# telemetry-r1.net
KiCad netlist of a schematic drawn in EAGLE
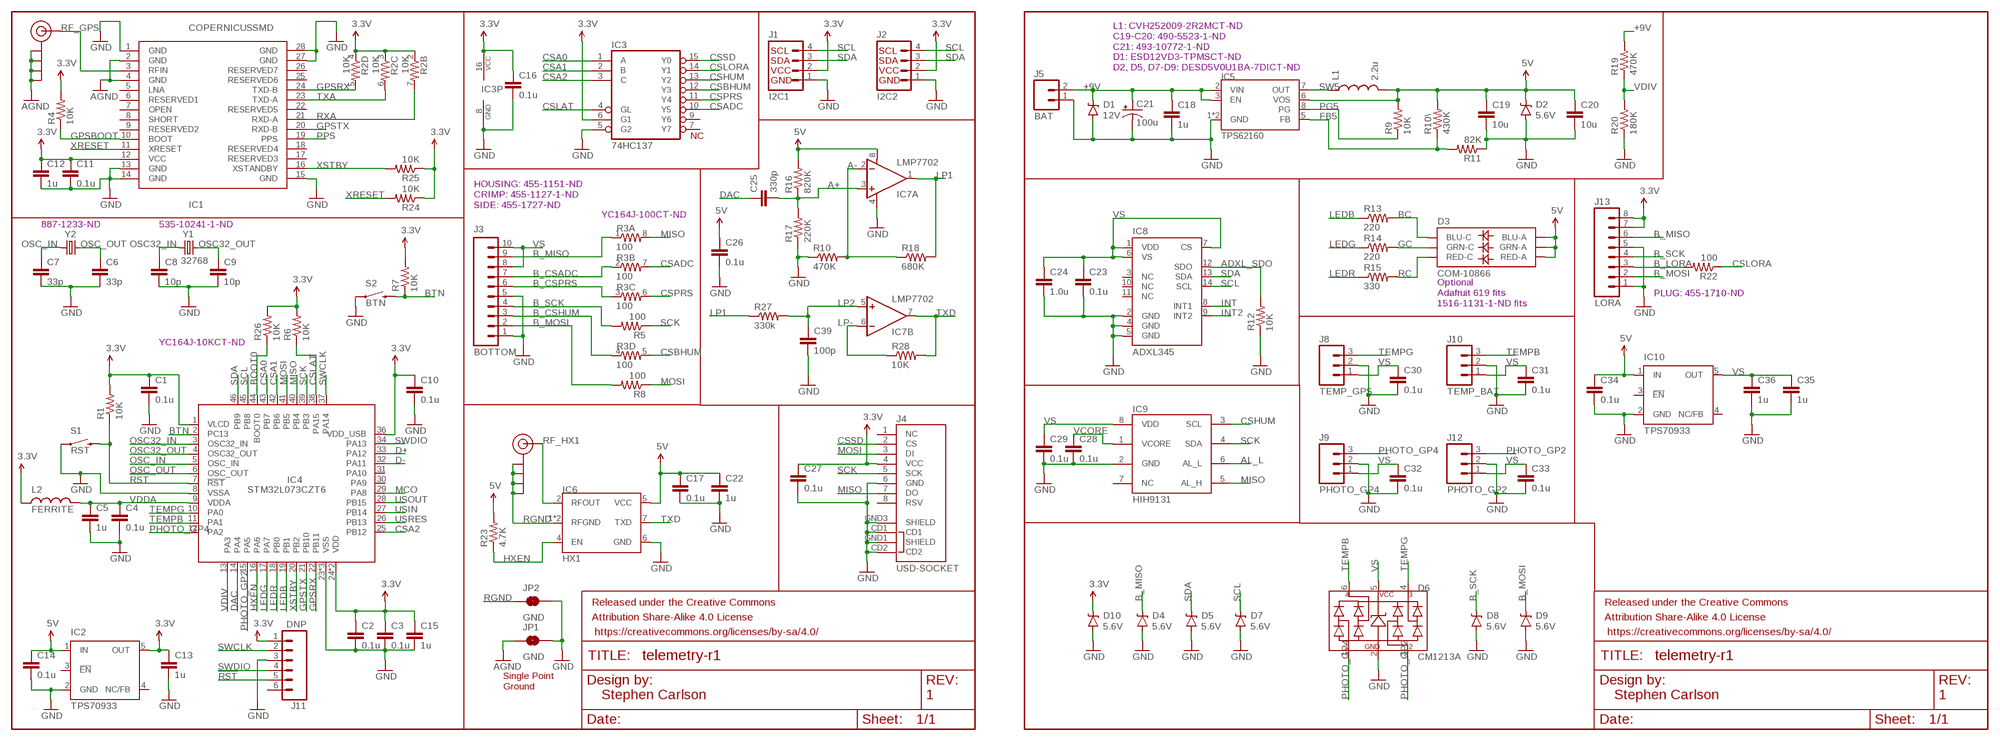
[diagram p0: schematic, sheet 1]

(export (version "E")
  (design (tool "Eeschema 10.0.6"))
  (components
    (comp (ref "C1")
      (value "0.1u")
      (footprint "eagle-import:0805")
      (libsource (lib "eagle-import") (part "CAP0805"))
    )
    (comp (ref "C2")
      (value "0.1u")
      (footprint "eagle-import:0805")
      (libsource (lib "eagle-import") (part "CAP0805"))
    )
    (comp (ref "C3")
      (value "0.1u")
      (footprint "eagle-import:0805")
      (libsource (lib "eagle-import") (part "CAP0805"))
    )
    (comp (ref "C4")
      (value "0.1u")
      (footprint "eagle-import:0805")
      (libsource (lib "eagle-import") (part "CAP0805"))
    )
    (comp (ref "C5")
      (value "1u")
      (footprint "eagle-import:0805")
      (libsource (lib "eagle-import") (part "CAP0805"))
    )
    (comp (ref "C6")
      (value "33p")
      (footprint "eagle-import:0805")
      (libsource (lib "eagle-import") (part "CAP0805"))
    )
    (comp (ref "C7")
      (value "33p")
      (footprint "eagle-import:0805")
      (libsource (lib "eagle-import") (part "CAP0805"))
    )
    (comp (ref "C8")
      (value "10p")
      (footprint "eagle-import:0805")
      (libsource (lib "eagle-import") (part "CAP0805"))
    )
    (comp (ref "C9")
      (value "10p")
      (footprint "eagle-import:0805")
      (libsource (lib "eagle-import") (part "CAP0805"))
    )
    (comp (ref "C10")
      (value "0.1u")
      (footprint "eagle-import:0805")
      (libsource (lib "eagle-import") (part "CAP0805"))
    )
    (comp (ref "C11")
      (value "0.1u")
      (footprint "eagle-import:0805")
      (libsource (lib "eagle-import") (part "CAP0805"))
    )
    (comp (ref "C12")
      (value "1u")
      (footprint "eagle-import:0805")
      (libsource (lib "eagle-import") (part "CAP0805"))
    )
    (comp (ref "C13")
      (value "1u")
      (footprint "eagle-import:0805")
      (libsource (lib "eagle-import") (part "CAP0805"))
    )
    (comp (ref "C14")
      (value "0.1u")
      (footprint "eagle-import:0805")
      (libsource (lib "eagle-import") (part "CAP0805"))
    )
    (comp (ref "C15")
      (value "1u")
      (footprint "eagle-import:0805")
      (libsource (lib "eagle-import") (part "CAP0805"))
    )
    (comp (ref "C16")
      (value "0.1u")
      (footprint "eagle-import:0805")
      (libsource (lib "eagle-import") (part "CAP0805"))
    )
    (comp (ref "C17")
      (value "0.1u")
      (footprint "eagle-import:0805")
      (libsource (lib "eagle-import") (part "CAP0805"))
    )
    (comp (ref "C18")
      (value "1u")
      (footprint "eagle-import:0805")
      (libsource (lib "eagle-import") (part "CAP0805"))
    )
    (comp (ref "C19")
      (value "10u")
      (footprint "eagle-import:0805")
      (libsource (lib "eagle-import") (part "CAP0805"))
    )
    (comp (ref "C20")
      (value "10u")
      (footprint "eagle-import:0805")
      (libsource (lib "eagle-import") (part "CAP0805"))
    )
    (comp (ref "C21")
      (value "100u")
      (footprint "eagle-import:CPOL-RADIAL-10UF-25V")
      (libsource (lib "eagle-import") (part "CAP_POLPTH2"))
    )
    (comp (ref "C22")
      (value "1u")
      (footprint "eagle-import:0805")
      (libsource (lib "eagle-import") (part "CAP0805"))
    )
    (comp (ref "C23")
      (value "0.1u")
      (footprint "eagle-import:0805")
      (libsource (lib "eagle-import") (part "CAP0805"))
    )
    (comp (ref "C24")
      (value "1.0u")
      (footprint "eagle-import:0805")
      (libsource (lib "eagle-import") (part "CAP0805"))
    )
    (comp (ref "C25")
      (value "330p")
      (footprint "eagle-import:0805")
      (libsource (lib "eagle-import") (part "CAP0805"))
    )
    (comp (ref "C26")
      (value "0.1u")
      (footprint "eagle-import:0805")
      (libsource (lib "eagle-import") (part "CAP0805"))
    )
    (comp (ref "C27")
      (value "0.1u")
      (footprint "eagle-import:0805")
      (libsource (lib "eagle-import") (part "CAP0805"))
    )
    (comp (ref "C28")
      (value "0.1u")
      (footprint "eagle-import:0805")
      (libsource (lib "eagle-import") (part "CAP0805"))
    )
    (comp (ref "C29")
      (value "0.1u")
      (footprint "eagle-import:0805")
      (libsource (lib "eagle-import") (part "CAP0805"))
    )
    (comp (ref "C30")
      (value "0.1u")
      (footprint "eagle-import:0805")
      (libsource (lib "eagle-import") (part "CAP0805"))
    )
    (comp (ref "C31")
      (value "0.1u")
      (footprint "eagle-import:0805")
      (libsource (lib "eagle-import") (part "CAP0805"))
    )
    (comp (ref "C32")
      (value "0.1u")
      (footprint "eagle-import:0805")
      (libsource (lib "eagle-import") (part "CAP0805"))
    )
    (comp (ref "C33")
      (value "0.1u")
      (footprint "eagle-import:0805")
      (libsource (lib "eagle-import") (part "CAP0805"))
    )
    (comp (ref "C34")
      (value "0.1u")
      (footprint "eagle-import:0805")
      (libsource (lib "eagle-import") (part "CAP0805"))
    )
    (comp (ref "C35")
      (value "1u")
      (footprint "eagle-import:0805")
      (libsource (lib "eagle-import") (part "CAP0805"))
    )
    (comp (ref "C36")
      (value "1u")
      (footprint "eagle-import:0805")
      (libsource (lib "eagle-import") (part "CAP0805"))
    )
    (comp (ref "C39")
      (value "100p")
      (footprint "eagle-import:0805")
      (libsource (lib "eagle-import") (part "CAP0805"))
    )
    (comp (ref "D1")
      (value "12V")
      (footprint "eagle-import:SOD-323")
      (libsource (lib "eagle-import") (part "DIODE-ZENER5.6V"))
    )
    (comp (ref "D2")
      (value "5.6V")
      (footprint "eagle-import:SOD-323")
      (libsource (lib "eagle-import") (part "DIODE-ZENER5.6V"))
    )
    (comp (ref "D3")
      (value "COM-10866")
      (footprint "eagle-import:LED-TRICOLOR-5050")
      (libsource (lib "eagle-import") (part "LED-TRICOLOR-5050NO_IC"))
    )
    (comp (ref "D4")
      (value "5.6V")
      (footprint "eagle-import:SOD-323")
      (libsource (lib "eagle-import") (part "DIODE-ZENER5.6V"))
    )
    (comp (ref "D5")
      (value "5.6V")
      (footprint "eagle-import:SOD-323")
      (libsource (lib "eagle-import") (part "DIODE-ZENER5.6V"))
    )
    (comp (ref "D6")
      (value "CM1213A")
      (footprint "eagle-import:SC70-6L")
      (libsource (lib "eagle-import") (part "CM1213A"))
    )
    (comp (ref "D7")
      (value "5.6V")
      (footprint "eagle-import:SOD-323")
      (libsource (lib "eagle-import") (part "DIODE-ZENER5.6V"))
    )
    (comp (ref "D8")
      (value "5.6V")
      (footprint "eagle-import:SOD-323")
      (libsource (lib "eagle-import") (part "DIODE-ZENER5.6V"))
    )
    (comp (ref "D9")
      (value "5.6V")
      (footprint "eagle-import:SOD-323")
      (libsource (lib "eagle-import") (part "DIODE-ZENER5.6V"))
    )
    (comp (ref "D10")
      (value "5.6V")
      (footprint "eagle-import:SOD-323")
      (libsource (lib "eagle-import") (part "DIODE-ZENER5.6V"))
    )
    (comp (ref "FRAME1")
      (value "FRAME-LETTERNO_PACKAGE")
      (footprint "eagle-import:DUMMY")
      (fields (field (name "DESIGNER") "Nobody"))
      (libsource (lib "eagle-import") (part "FRAME-LETTERNO_PACKAGE"))
    )
    (comp (ref "FRAME2")
      (value "FRAME-LETTERNO_PACKAGE")
      (footprint "eagle-import:DUMMY")
      (fields (field (name "DESIGNER") "Nobody"))
      (libsource (lib "eagle-import") (part "FRAME-LETTERNO_PACKAGE"))
    )
    (comp (ref "IC1")
      (value "COPERNICUSSMD")
      (footprint "eagle-import:COPERNICUS")
      (libsource (lib "eagle-import") (part "COPERNICUSSMD"))
    )
    (comp (ref "IC2")
      (value "TPS70933")
      (footprint "eagle-import:SOT23-DBV")
      (fields (field (name "MF") "TEXAS INSTRUMENTS") (field (name "MPN") "TPS77033DBVT"))
      (libsource (lib "eagle-import") (part "TPS77033"))
    )
    (comp (ref "IC3")
      (value "74HC137")
      (footprint "eagle-import:TSSOP16")
      (libsource (lib "eagle-import") (part "74137PWLS"))
    )
    (comp (ref "IC4")
      (value "STM32L073CZT6")
      (footprint "eagle-import:TQFP48")
      (libsource (lib "eagle-import") (part "STM32L07C"))
    )
    (comp (ref "IC5")
      (value "TPS62160")
      (footprint "eagle-import:MSOP8")
      (libsource (lib "eagle-import") (part "TPS62160"))
    )
    (comp (ref "IC6")
      (value "HX1")
      (footprint "eagle-import:HX1")
      (libsource (lib "eagle-import") (part "HX1"))
    )
    (comp (ref "IC7")
      (value "LMP7702")
      (footprint "eagle-import:SO08")
      (libsource (lib "eagle-import") (part "OPAMP-DUALU"))
    )
    (comp (ref "IC8")
      (value "ADXL345")
      (footprint "eagle-import:LGA14")
      (libsource (lib "eagle-import") (part "ADXL345"))
    )
    (comp (ref "IC9")
      (value "HIH9131")
      (footprint "eagle-import:SOIC8")
      (libsource (lib "eagle-import") (part "HIH6131"))
    )
    (comp (ref "IC10")
      (value "TPS70933")
      (footprint "eagle-import:SOT23-DBV")
      (fields (field (name "MF") "TEXAS INSTRUMENTS") (field (name "MPN") "TPS77033DBVT"))
      (libsource (lib "eagle-import") (part "TPS77033"))
    )
    (comp (ref "J1")
      (value "I2C1")
      (footprint "eagle-import:1X04_NO_SILK")
      (libsource (lib "eagle-import") (part "I2C_STANDARD_NO_SILK"))
    )
    (comp (ref "J2")
      (value "I2C2")
      (footprint "eagle-import:1X04_NO_SILK")
      (libsource (lib "eagle-import") (part "I2C_STANDARD_NO_SILK"))
    )
    (comp (ref "J3")
      (value "BOTTOM")
      (footprint "eagle-import:1X10-2MM")
      (libsource (lib "eagle-import") (part "M102MM"))
    )
    (comp (ref "J4")
      (value "USD-SOCKET")
      (footprint "eagle-import:MICROSD_1_1")
      (libsource (lib "eagle-import") (part "USD-SOCKET"))
    )
    (comp (ref "J5")
      (value "BAT")
      (footprint "eagle-import:1X02")
      (libsource (lib "eagle-import") (part "M02PTH"))
    )
    (comp (ref "J6")
      (value "SMA_EDGE")
      (footprint "eagle-import:SMA-EDGE")
      (libsource (lib "eagle-import") (part "SMA_EDGE"))
    )
    (comp (ref "J7")
      (value "SMA_EDGE")
      (footprint "eagle-import:SMA-EDGE")
      (libsource (lib "eagle-import") (part "SMA_EDGE"))
    )
    (comp (ref "J8")
      (value "TEMP_GPS")
      (footprint "eagle-import:JST-3-PTH")
      (libsource (lib "eagle-import") (part "M03JST-PTH"))
    )
    (comp (ref "J9")
      (value "PHOTO_GP4")
      (footprint "eagle-import:JST-3-PTH")
      (libsource (lib "eagle-import") (part "M03JST-PTH"))
    )
    (comp (ref "J10")
      (value "TEMP_BAT")
      (footprint "eagle-import:JST-3-PTH")
      (libsource (lib "eagle-import") (part "M03JST-PTH"))
    )
    (comp (ref "J11")
      (value "DNP")
      (footprint "eagle-import:1X06_LOCK")
      (libsource (lib "eagle-import") (part "M06LOCK"))
    )
    (comp (ref "J12")
      (value "PHOTO_GP2")
      (footprint "eagle-import:JST-3-PTH")
      (libsource (lib "eagle-import") (part "M03JST-PTH"))
    )
    (comp (ref "J13")
      (value "LORA")
      (footprint "eagle-import:1X08-2MM")
      (libsource (lib "eagle-import") (part "1X08"))
    )
    (comp (ref "JP1")
      (value "GND")
      (footprint "eagle-import:PAD-JUMPER-2-NC_BY_TRACE_YES_SILK")
      (libsource (lib "eagle-import") (part "JUMPER-PAD-2-NC_BY_TRACE"))
    )
    (comp (ref "JP2")
      (value "GND")
      (footprint "eagle-import:PAD-JUMPER-2-NC_BY_TRACE_YES_SILK")
      (libsource (lib "eagle-import") (part "JUMPER-PAD-2-NC_BY_TRACE"))
    )
    (comp (ref "L1")
      (value "2.2u")
      (footprint "eagle-import:1008")
      (libsource (lib "eagle-import") (part "INDUCTOR1008"))
    )
    (comp (ref "L2")
      (value "FERRITE")
      (footprint "eagle-import:1206")
      (libsource (lib "eagle-import") (part "INDUCTOR1206"))
    )
    (comp (ref "R1")
      (value "10K")
      (footprint "eagle-import:0805")
      (libsource (lib "eagle-import") (part "RESISTOR0805-RES"))
    )
    (comp (ref "R2")
      (value "10K")
      (footprint "eagle-import:0603-ARV")
      (libsource (lib "eagle-import") (part "RESISTOR-ARRAY0603-ARV"))
    )
    (comp (ref "R3")
      (value "100")
      (footprint "eagle-import:0603-ARV")
      (libsource (lib "eagle-import") (part "RESISTOR-ARRAY0603-ARV"))
    )
    (comp (ref "R4")
      (value "10K")
      (footprint "eagle-import:0805")
      (libsource (lib "eagle-import") (part "RESISTOR0805-RES"))
    )
    (comp (ref "R5")
      (value "100")
      (footprint "eagle-import:0805")
      (libsource (lib "eagle-import") (part "RESISTOR0805-RES"))
    )
    (comp (ref "R6")
      (value "10K")
      (footprint "eagle-import:0805")
      (libsource (lib "eagle-import") (part "RESISTOR0805-RES"))
    )
    (comp (ref "R7")
      (value "10K")
      (footprint "eagle-import:0805")
      (libsource (lib "eagle-import") (part "RESISTOR0805-RES"))
    )
    (comp (ref "R8")
      (value "100")
      (footprint "eagle-import:0805")
      (libsource (lib "eagle-import") (part "RESISTOR0805-RES"))
    )
    (comp (ref "R9")
      (value "10K")
      (footprint "eagle-import:0805")
      (libsource (lib "eagle-import") (part "RESISTOR0805-RES"))
    )
    (comp (ref "R10")
      (value "470K")
      (footprint "eagle-import:0805")
      (libsource (lib "eagle-import") (part "RESISTOR0805-RES"))
    )
    (comp (ref "R10\\")
      (value "430K")
      (footprint "eagle-import:0805")
      (libsource (lib "eagle-import") (part "RESISTOR0805-RES"))
    )
    (comp (ref "R11")
      (value "82K")
      (footprint "eagle-import:0805")
      (libsource (lib "eagle-import") (part "RESISTOR0805-RES"))
    )
    (comp (ref "R12")
      (value "10K")
      (footprint "eagle-import:0805")
      (libsource (lib "eagle-import") (part "RESISTOR0805-RES"))
    )
    (comp (ref "R13")
      (value "220")
      (footprint "eagle-import:0805")
      (libsource (lib "eagle-import") (part "RESISTOR0805-RES"))
    )
    (comp (ref "R14")
      (value "220")
      (footprint "eagle-import:0805")
      (libsource (lib "eagle-import") (part "RESISTOR0805-RES"))
    )
    (comp (ref "R15")
      (value "330")
      (footprint "eagle-import:0805")
      (libsource (lib "eagle-import") (part "RESISTOR0805-RES"))
    )
    (comp (ref "R16")
      (value "820K")
      (footprint "eagle-import:0805")
      (libsource (lib "eagle-import") (part "RESISTOR0805-RES"))
    )
    (comp (ref "R17")
      (value "220K")
      (footprint "eagle-import:0805")
      (libsource (lib "eagle-import") (part "RESISTOR0805-RES"))
    )
    (comp (ref "R18")
      (value "680K")
      (footprint "eagle-import:0805")
      (libsource (lib "eagle-import") (part "RESISTOR0805-RES"))
    )
    (comp (ref "R19")
      (value "470K")
      (footprint "eagle-import:0805")
      (libsource (lib "eagle-import") (part "RESISTOR0805-RES"))
    )
    (comp (ref "R20")
      (value "180K")
      (footprint "eagle-import:0805")
      (libsource (lib "eagle-import") (part "RESISTOR0805-RES"))
    )
    (comp (ref "R22")
      (value "100")
      (footprint "eagle-import:0805")
      (libsource (lib "eagle-import") (part "RESISTOR0805-RES"))
    )
    (comp (ref "R23")
      (value "4.7K")
      (footprint "eagle-import:0805")
      (libsource (lib "eagle-import") (part "RESISTOR0805-RES"))
    )
    (comp (ref "R24")
      (value "10K")
      (footprint "eagle-import:0805")
      (libsource (lib "eagle-import") (part "RESISTOR0805-RES"))
    )
    (comp (ref "R25")
      (value "10K")
      (footprint "eagle-import:0805")
      (libsource (lib "eagle-import") (part "RESISTOR0805-RES"))
    )
    (comp (ref "R26")
      (value "10K")
      (footprint "eagle-import:0805")
      (libsource (lib "eagle-import") (part "RESISTOR0805-RES"))
    )
    (comp (ref "R27")
      (value "330k")
      (footprint "eagle-import:0805")
      (libsource (lib "eagle-import") (part "RESISTOR0805-RES"))
    )
    (comp (ref "R28")
      (value "10K")
      (footprint "eagle-import:0805")
      (libsource (lib "eagle-import") (part "RESISTOR0805-RES"))
    )
    (comp (ref "S1")
      (value "RST")
      (footprint "eagle-import:TACTILE-PTH-THIN")
      (libsource (lib "eagle-import") (part "SWITCH"))
    )
    (comp (ref "S2")
      (value "BTN")
      (footprint "eagle-import:TACTILE-PTH-THIN")
      (libsource (lib "eagle-import") (part "SWITCH"))
    )
    (comp (ref "Y1")
      (value "32768")
      (footprint "eagle-import:ABS25")
      (libsource (lib "eagle-import") (part "CRYSTAL"))
    )
    (comp (ref "Y2")
      (value "8M")
      (footprint "eagle-import:HC49UP")
      (libsource (lib "eagle-import") (part "CRYSTALSMD"))
    )
  )
  (nets
    (net (code "1") (name "/+9V") (class "Default")
      (node (ref "C18") (pin "1") (pinfunction "1_1") (pintype "passive"))
      (node (ref "C21") (pin "1") (pinfunction "+_1") (pintype "passive"))
      (node (ref "D1") (pin "C") (pinfunction "C_C") (pintype "passive"))
      (node (ref "IC5") (pin "2") (pinfunction "VIN_2") (pintype "power_in"))
      (node (ref "IC5") (pin "3") (pinfunction "EN_3") (pintype "input"))
      (node (ref "J5") (pin "2") (pinfunction "2_2") (pintype "passive"))
      (node (ref "R19") (pin "2") (pinfunction "2_2") (pintype "passive"))
    )
    (net (code "2") (name "/A+") (class "Default")
      (node (ref "C25") (pin "2") (pinfunction "2_2") (pintype "passive"))
      (node (ref "IC7") (pin "3") (pinfunction "+IN_3") (pintype "input"))
      (node (ref "R16") (pin "1") (pinfunction "1_1") (pintype "passive"))
      (node (ref "R17") (pin "2") (pinfunction "2_2") (pintype "passive"))
    )
    (net (code "3") (name "/A-") (class "Default")
      (node (ref "IC7") (pin "2") (pinfunction "-IN_2") (pintype "input"))
      (node (ref "R10") (pin "2") (pinfunction "2_2") (pintype "passive"))
      (node (ref "R18") (pin "1") (pinfunction "1_1") (pintype "passive"))
    )
    (net (code "4") (name "/ADXL_SDO") (class "Default")
      (node (ref "IC8") (pin "12") (pinfunction "SDO_12") (pintype "bidirectional"))
      (node (ref "R12") (pin "2") (pinfunction "2_2") (pintype "passive"))
    )
    (net (code "5") (name "/AL_L") (class "Default")
      (node (ref "IC9") (pin "6") (pinfunction "AL_L_6") (pintype "bidirectional"))
    )
    (net (code "6") (name "/BC") (class "Default")
      (node (ref "D3") (pin "4") (pinfunction "BLU-C_4") (pintype "bidirectional"))
      (node (ref "R13") (pin "2") (pinfunction "2_2") (pintype "passive"))
    )
    (net (code "7") (name "/BOOT0") (class "Default")
      (node (ref "IC4") (pin "44") (pinfunction "BOOT0_44") (pintype "input"))
      (node (ref "R26") (pin "1") (pinfunction "1_1") (pintype "passive"))
    )
    (net (code "8") (name "/BTN") (class "Default")
      (node (ref "IC4") (pin "2") (pinfunction "PC13_2") (pintype "bidirectional"))
      (node (ref "R7") (pin "1") (pinfunction "1_1") (pintype "passive"))
      (node (ref "S2") (pin "2") (pinfunction "2_2") (pintype "passive"))
    )
    (net (code "9") (name "/B_CSADC") (class "Default")
      (node (ref "J3") (pin "7") (pinfunction "7_7") (pintype "passive"))
      (node (ref "R3") (pin "2") (pinfunction "1_2") (pintype "passive"))
    )
    (net (code "10") (name "/B_CSHUM") (class "Default")
      (node (ref "J3") (pin "3") (pinfunction "3_3") (pintype "passive"))
      (node (ref "R3") (pin "4") (pinfunction "1_4") (pintype "passive"))
    )
    (net (code "11") (name "/B_CSPRS") (class "Default")
      (node (ref "J3") (pin "6") (pinfunction "6_6") (pintype "passive"))
      (node (ref "R3") (pin "3") (pinfunction "1_3") (pintype "passive"))
    )
    (net (code "12") (name "/B_LORA") (class "Default")
      (node (ref "J13") (pin "3") (pinfunction "3_3") (pintype "passive"))
      (node (ref "R22") (pin "2") (pinfunction "2_2") (pintype "passive"))
    )
    (net (code "13") (name "/B_MISO") (class "Default")
      (node (ref "D4") (pin "C") (pinfunction "C_C") (pintype "passive"))
      (node (ref "J13") (pin "6") (pinfunction "6_6") (pintype "passive"))
      (node (ref "J3") (pin "9") (pinfunction "9_9") (pintype "passive"))
      (node (ref "R3") (pin "1") (pinfunction "1_1") (pintype "passive"))
    )
    (net (code "14") (name "/B_MOSI") (class "Default")
      (node (ref "D9") (pin "C") (pinfunction "C_C") (pintype "passive"))
      (node (ref "J13") (pin "2") (pinfunction "2_2") (pintype "passive"))
      (node (ref "J3") (pin "2") (pinfunction "2_2") (pintype "passive"))
      (node (ref "R8") (pin "2") (pinfunction "2_2") (pintype "passive"))
    )
    (net (code "15") (name "/B_SCK") (class "Default")
      (node (ref "D8") (pin "C") (pinfunction "C_C") (pintype "passive"))
      (node (ref "J13") (pin "4") (pinfunction "4_4") (pintype "passive"))
      (node (ref "J3") (pin "4") (pinfunction "4_4") (pintype "passive"))
      (node (ref "R5") (pin "2") (pinfunction "2_2") (pintype "passive"))
    )
    (net (code "16") (name "/CSA0") (class "Default")
      (node (ref "IC3") (pin "1") (pinfunction "A_1") (pintype "input"))
      (node (ref "IC4") (pin "43") (pinfunction "PB7_43") (pintype "bidirectional"))
    )
    (net (code "17") (name "/CSA1") (class "Default")
      (node (ref "IC3") (pin "2") (pinfunction "B_2") (pintype "input"))
      (node (ref "IC4") (pin "42") (pinfunction "PB6_42") (pintype "bidirectional"))
    )
    (net (code "18") (name "/CSA2") (class "Default")
      (node (ref "IC3") (pin "3") (pinfunction "C_3") (pintype "input"))
      (node (ref "IC4") (pin "25") (pinfunction "PB12_25") (pintype "bidirectional"))
    )
    (net (code "19") (name "/CSADC") (class "Default")
      (node (ref "IC3") (pin "10") (pinfunction "Y5_10") (pintype "output"))
      (node (ref "R3") (pin "7") (pinfunction "2_7") (pintype "passive"))
    )
    (net (code "20") (name "/CSBHUM") (class "Default")
      (node (ref "IC3") (pin "12") (pinfunction "Y3_12") (pintype "output"))
      (node (ref "R3") (pin "5") (pinfunction "2_5") (pintype "passive"))
    )
    (net (code "21") (name "/CSHUM") (class "Default")
      (node (ref "IC3") (pin "13") (pinfunction "Y2_13") (pintype "output"))
      (node (ref "IC9") (pin "3") (pinfunction "SCL_3") (pintype "bidirectional"))
    )
    (net (code "22") (name "/CSLAT") (class "Default")
      (node (ref "IC3") (pin "4") (pinfunction "GL_4") (pintype "input"))
      (node (ref "IC4") (pin "38") (pinfunction "PA15_38") (pintype "bidirectional"))
      (node (ref "R6") (pin "1") (pinfunction "1_1") (pintype "passive"))
    )
    (net (code "23") (name "/CSLORA") (class "Default")
      (node (ref "IC3") (pin "14") (pinfunction "Y1_14") (pintype "output"))
      (node (ref "R22") (pin "1") (pinfunction "1_1") (pintype "passive"))
    )
    (net (code "24") (name "/CSPRS") (class "Default")
      (node (ref "IC3") (pin "11") (pinfunction "Y4_11") (pintype "output"))
      (node (ref "R3") (pin "6") (pinfunction "2_6") (pintype "passive"))
    )
    (net (code "25") (name "/CSSD") (class "Default")
      (node (ref "IC3") (pin "15") (pinfunction "Y0_15") (pintype "output"))
      (node (ref "J4") (pin "2") (pinfunction "CS_2") (pintype "bidirectional"))
    )
    (net (code "26") (name "/D+") (class "Default")
      (node (ref "IC4") (pin "33") (pinfunction "PA12_33") (pintype "bidirectional"))
    )
    (net (code "27") (name "/D-") (class "Default")
      (node (ref "IC4") (pin "32") (pinfunction "PA11_32") (pintype "bidirectional"))
    )
    (net (code "28") (name "/DAC") (class "Default")
      (node (ref "C25") (pin "1") (pinfunction "1_1") (pintype "passive"))
      (node (ref "IC4") (pin "14") (pinfunction "PA4_14") (pintype "bidirectional"))
    )
    (net (code "29") (name "/FB5") (class "Default")
      (node (ref "IC5") (pin "5") (pinfunction "FB_5") (pintype "input"))
      (node (ref "R10\\") (pin "1") (pinfunction "1_1") (pintype "passive"))
      (node (ref "R11") (pin "2") (pinfunction "2_2") (pintype "passive"))
    )
    (net (code "30") (name "/GC") (class "Default")
      (node (ref "D3") (pin "6") (pinfunction "GRN-C_6") (pintype "bidirectional"))
      (node (ref "R14") (pin "2") (pinfunction "2_2") (pintype "passive"))
    )
    (net (code "31") (name "/GPSBOOT") (class "Default")
      (node (ref "IC1") (pin "10") (pinfunction "BOOT_10") (pintype "bidirectional"))
      (node (ref "R4") (pin "1") (pinfunction "1_1") (pintype "passive"))
    )
    (net (code "32") (name "/GPSRX") (class "Default")
      (node (ref "IC1") (pin "24") (pinfunction "TXD-B_24") (pintype "bidirectional"))
      (node (ref "IC4") (pin "22") (pinfunction "PB11_22") (pintype "bidirectional"))
      (node (ref "R2") (pin "5") (pinfunction "2_5") (pintype "passive"))
    )
    (net (code "33") (name "/GPSTX") (class "Default")
      (node (ref "IC1") (pin "20") (pinfunction "RXD-B_20") (pintype "bidirectional"))
      (node (ref "IC4") (pin "21") (pinfunction "PB10_21") (pintype "bidirectional"))
    )
    (net (code "34") (name "/HXEN") (class "Default")
      (node (ref "IC4") (pin "16") (pinfunction "PA6_16") (pintype "bidirectional"))
      (node (ref "IC6") (pin "4") (pinfunction "EN_4") (pintype "input"))
      (node (ref "R23") (pin "1") (pinfunction "1_1") (pintype "passive"))
    )
    (net (code "35") (name "/INT") (class "Default")
      (node (ref "IC8") (pin "8") (pinfunction "INT1_8") (pintype "bidirectional"))
    )
    (net (code "36") (name "/INT2") (class "Default")
      (node (ref "IC8") (pin "9") (pinfunction "INT2_9") (pintype "bidirectional"))
    )
    (net (code "37") (name "/LEDB") (class "Default")
      (node (ref "IC4") (pin "19") (pinfunction "PB1_19") (pintype "bidirectional"))
      (node (ref "R13") (pin "1") (pinfunction "1_1") (pintype "passive"))
    )
    (net (code "38") (name "/LEDG") (class "Default")
      (node (ref "IC4") (pin "17") (pinfunction "PA7_17") (pintype "bidirectional"))
      (node (ref "R14") (pin "1") (pinfunction "1_1") (pintype "passive"))
    )
    (net (code "39") (name "/LEDR") (class "Default")
      (node (ref "IC4") (pin "18") (pinfunction "PB0_18") (pintype "bidirectional"))
      (node (ref "R15") (pin "1") (pinfunction "1_1") (pintype "passive"))
    )
    (net (code "40") (name "/LP-") (class "Default")
      (node (ref "IC7") (pin "6") (pinfunction "-IN_6") (pintype "input"))
      (node (ref "R28") (pin "1") (pinfunction "1_1") (pintype "passive"))
    )
    (net (code "41") (name "/LP1") (class "Default")
      (node (ref "IC7") (pin "1") (pinfunction "OUT_1") (pintype "output"))
      (node (ref "R18") (pin "2") (pinfunction "2_2") (pintype "passive"))
      (node (ref "R27") (pin "1") (pinfunction "1_1") (pintype "passive"))
    )
    (net (code "42") (name "/LP2") (class "Default")
      (node (ref "C39") (pin "1") (pinfunction "1_1") (pintype "passive"))
      (node (ref "IC7") (pin "5") (pinfunction "+IN_5") (pintype "input"))
      (node (ref "R27") (pin "2") (pinfunction "2_2") (pintype "passive"))
    )
    (net (code "43") (name "/MCO") (class "Default")
      (node (ref "IC4") (pin "29") (pinfunction "PA8_29") (pintype "bidirectional"))
    )
    (net (code "44") (name "/MISO") (class "Default")
      (node (ref "IC4") (pin "40") (pinfunction "PB4_40") (pintype "bidirectional"))
      (node (ref "IC9") (pin "5") (pinfunction "AL_H_5") (pintype "bidirectional"))
      (node (ref "J4") (pin "7") (pinfunction "DO_7") (pintype "bidirectional"))
      (node (ref "R3") (pin "8") (pinfunction "2_8") (pintype "passive"))
    )
    (net (code "45") (name "/MOSI") (class "Default")
      (node (ref "IC4") (pin "41") (pinfunction "PB5_41") (pintype "bidirectional"))
      (node (ref "J4") (pin "3") (pinfunction "DI_3") (pintype "bidirectional"))
      (node (ref "R8") (pin "1") (pinfunction "1_1") (pintype "passive"))
    )
    (net (code "46") (name "/OSC32_IN") (class "Default")
      (node (ref "C8") (pin "1") (pinfunction "1_1") (pintype "passive"))
      (node (ref "IC4") (pin "3") (pinfunction "OSC32_IN_3") (pintype "bidirectional"))
      (node (ref "Y1") (pin "1") (pinfunction "1_1") (pintype "passive"))
    )
    (net (code "47") (name "/OSC32_OUT") (class "Default")
      (node (ref "C9") (pin "1") (pinfunction "1_1") (pintype "passive"))
      (node (ref "IC4") (pin "4") (pinfunction "OSC32_OUT_4") (pintype "bidirectional"))
      (node (ref "Y1") (pin "4") (pinfunction "2_4") (pintype "passive"))
    )
    (net (code "48") (name "/OSC_IN") (class "Default")
      (node (ref "C7") (pin "1") (pinfunction "1_1") (pintype "passive"))
      (node (ref "IC4") (pin "5") (pinfunction "OSC_IN_5") (pintype "bidirectional"))
      (node (ref "Y2") (pin "1") (pinfunction "1_1") (pintype "passive"))
    )
    (net (code "49") (name "/OSC_OUT") (class "Default")
      (node (ref "C6") (pin "1") (pinfunction "1_1") (pintype "passive"))
      (node (ref "IC4") (pin "6") (pinfunction "OSC_OUT_6") (pintype "bidirectional"))
      (node (ref "Y2") (pin "2") (pinfunction "2_2") (pintype "passive"))
    )
    (net (code "50") (name "/PG5") (class "Default")
      (node (ref "IC5") (pin "8") (pinfunction "PG_8") (pintype "open_collector"))
      (node (ref "R9") (pin "1") (pinfunction "1_1") (pintype "passive"))
    )
    (net (code "51") (name "/PHOTO_GP2") (class "Default")
      (node (ref "D6") (pin "3") (pinfunction "CH2_3") (pintype "passive"))
      (node (ref "IC4") (pin "15") (pinfunction "PA5_15") (pintype "bidirectional"))
      (node (ref "J12") (pin "3") (pinfunction "3_3") (pintype "passive"))
    )
    (net (code "52") (name "/PHOTO_GP4") (class "Default")
      (node (ref "D6") (pin "1") (pinfunction "CH1_1") (pintype "passive"))
      (node (ref "IC4") (pin "12") (pinfunction "PA2_12") (pintype "bidirectional"))
      (node (ref "J9") (pin "3") (pinfunction "3_3") (pintype "passive"))
    )
    (net (code "53") (name "/PPS") (class "Default")
      (node (ref "IC1") (pin "19") (pinfunction "PPS_19") (pintype "bidirectional"))
    )
    (net (code "54") (name "/RC") (class "Default")
      (node (ref "D3") (pin "5") (pinfunction "RED-C_5") (pintype "bidirectional"))
      (node (ref "R15") (pin "2") (pinfunction "2_2") (pintype "passive"))
    )
    (net (code "55") (name "/RF_GPS") (class "Default")
      (node (ref "IC1") (pin "3") (pinfunction "RFIN_3") (pintype "bidirectional"))
      (node (ref "J7") (pin "SIG") (pinfunction "SIGNAL_SIG") (pintype "bidirectional"))
    )
    (net (code "56") (name "/RF_HX1") (class "Default")
      (node (ref "IC6") (pin "2") (pinfunction "RFOUT_2") (pintype "output"))
      (node (ref "J6") (pin "SIG") (pinfunction "SIGNAL_SIG") (pintype "bidirectional"))
    )
    (net (code "57") (name "/RGND") (class "Default")
      (node (ref "IC6") (pin "1") (pinfunction "RFGND_1") (pintype "power_in"))
      (node (ref "IC6") (pin "3") (pinfunction "RFGND_3") (pintype "power_in"))
      (node (ref "J6") (pin "GND@0") (pinfunction "GND_GND@0") (pintype "bidirectional"))
      (node (ref "J6") (pin "GND@1") (pinfunction "GND_GND@1") (pintype "bidirectional"))
      (node (ref "J6") (pin "GND@2") (pinfunction "GND_GND@2") (pintype "bidirectional"))
      (node (ref "J6") (pin "GND@3") (pinfunction "GND_GND@3") (pintype "bidirectional"))
      (node (ref "JP2") (pin "1") (pinfunction "1_1") (pintype "passive"))
    )
    (net (code "58") (name "/RXA") (class "Default")
      (node (ref "IC1") (pin "21") (pinfunction "RXD-A_21") (pintype "bidirectional"))
      (node (ref "R2") (pin "7") (pinfunction "2_7") (pintype "passive"))
    )
    (net (code "59") (name "/SCK") (class "Default")
      (node (ref "IC4") (pin "39") (pinfunction "PB3_39") (pintype "bidirectional"))
      (node (ref "IC9") (pin "4") (pinfunction "SDA_4") (pintype "bidirectional"))
      (node (ref "J4") (pin "5") (pinfunction "SCK_5") (pintype "bidirectional"))
      (node (ref "R5") (pin "1") (pinfunction "1_1") (pintype "passive"))
    )
    (net (code "60") (name "/SCL") (class "Default")
      (node (ref "D7") (pin "C") (pinfunction "C_C") (pintype "passive"))
      (node (ref "IC4") (pin "45") (pinfunction "PB8_45") (pintype "bidirectional"))
      (node (ref "IC8") (pin "14") (pinfunction "SCL_14") (pintype "bidirectional"))
      (node (ref "J1") (pin "4") (pinfunction "4_4") (pintype "passive"))
      (node (ref "J2") (pin "4") (pinfunction "4_4") (pintype "passive"))
    )
    (net (code "61") (name "/SDA") (class "Default")
      (node (ref "D5") (pin "C") (pinfunction "C_C") (pintype "passive"))
      (node (ref "IC4") (pin "46") (pinfunction "PB9_46") (pintype "bidirectional"))
      (node (ref "IC8") (pin "13") (pinfunction "SDA_13") (pintype "bidirectional"))
      (node (ref "J1") (pin "3") (pinfunction "3_3") (pintype "passive"))
      (node (ref "J2") (pin "3") (pinfunction "3_3") (pintype "passive"))
    )
    (net (code "62") (name "/SW5") (class "Default")
      (node (ref "IC5") (pin "7") (pinfunction "OUT_7") (pintype "output"))
      (node (ref "L1") (pin "1") (pinfunction "1_1") (pintype "passive"))
    )
    (net (code "63") (name "/SWCLK") (class "Default")
      (node (ref "IC4") (pin "37") (pinfunction "PA14_37") (pintype "bidirectional"))
      (node (ref "J11") (pin "2") (pinfunction "2_2") (pintype "passive"))
    )
    (net (code "64") (name "/SWDIO") (class "Default")
      (node (ref "IC4") (pin "34") (pinfunction "PA13_34") (pintype "bidirectional"))
      (node (ref "J11") (pin "4") (pinfunction "4_4") (pintype "passive"))
    )
    (net (code "65") (name "/TEMPB") (class "Default")
      (node (ref "D6") (pin "6") (pinfunction "CH4_6") (pintype "passive"))
      (node (ref "IC4") (pin "11") (pinfunction "PA1_11") (pintype "bidirectional"))
      (node (ref "J10") (pin "3") (pinfunction "3_3") (pintype "passive"))
    )
    (net (code "66") (name "/TEMPG") (class "Default")
      (node (ref "D6") (pin "4") (pinfunction "CH3_4") (pintype "passive"))
      (node (ref "IC4") (pin "10") (pinfunction "PA0_10") (pintype "bidirectional"))
      (node (ref "J8") (pin "3") (pinfunction "3_3") (pintype "passive"))
    )
    (net (code "67") (name "/TXA") (class "Default")
      (node (ref "IC1") (pin "23") (pinfunction "TXD-A_23") (pintype "bidirectional"))
      (node (ref "R2") (pin "6") (pinfunction "2_6") (pintype "passive"))
    )
    (net (code "68") (name "/TXD") (class "Default")
      (node (ref "IC6") (pin "7") (pinfunction "TXD_7") (pintype "input"))
      (node (ref "IC7") (pin "7") (pinfunction "OUT_7") (pintype "output"))
      (node (ref "R28") (pin "2") (pinfunction "2_2") (pintype "passive"))
    )
    (net (code "69") (name "/USIN") (class "Default")
      (node (ref "IC4") (pin "27") (pinfunction "PB14_27") (pintype "bidirectional"))
    )
    (net (code "70") (name "/USOUT") (class "Default")
      (node (ref "IC4") (pin "28") (pinfunction "PB15_28") (pintype "bidirectional"))
    )
    (net (code "71") (name "/USRES") (class "Default")
      (node (ref "IC4") (pin "26") (pinfunction "PB13_26") (pintype "bidirectional"))
    )
    (net (code "72") (name "/VCORE") (class "Default")
      (node (ref "C28") (pin "1") (pinfunction "1_1") (pintype "passive"))
      (node (ref "IC9") (pin "1") (pinfunction "VCORE_1") (pintype "bidirectional"))
    )
    (net (code "73") (name "/VDDA") (class "Default")
      (node (ref "C4") (pin "1") (pinfunction "1_1") (pintype "passive"))
      (node (ref "C5") (pin "1") (pinfunction "1_1") (pintype "passive"))
      (node (ref "IC4") (pin "9") (pinfunction "VDDA_9") (pintype "power_in"))
      (node (ref "L2") (pin "2") (pinfunction "2_2") (pintype "passive"))
    )
    (net (code "74") (name "/VDIV") (class "Default")
      (node (ref "IC4") (pin "13") (pinfunction "PA3_13") (pintype "bidirectional"))
      (node (ref "R19") (pin "1") (pinfunction "1_1") (pintype "passive"))
      (node (ref "R20") (pin "2") (pinfunction "2_2") (pintype "passive"))
    )
    (net (code "75") (name "/VS") (class "Default")
      (node (ref "C23") (pin "1") (pinfunction "1_1") (pintype "passive"))
      (node (ref "C24") (pin "1") (pinfunction "1_1") (pintype "passive"))
      (node (ref "C29") (pin "1") (pinfunction "1_1") (pintype "passive"))
      (node (ref "C30") (pin "1") (pinfunction "1_1") (pintype "passive"))
      (node (ref "C31") (pin "1") (pinfunction "1_1") (pintype "passive"))
      (node (ref "C32") (pin "1") (pinfunction "1_1") (pintype "passive"))
      (node (ref "C33") (pin "1") (pinfunction "1_1") (pintype "passive"))
      (node (ref "C35") (pin "1") (pinfunction "1_1") (pintype "passive"))
      (node (ref "C36") (pin "1") (pinfunction "1_1") (pintype "passive"))
      (node (ref "D6") (pin "5") (pinfunction "VCC_5") (pintype "power_in"))
      (node (ref "IC10") (pin "5") (pinfunction "OUT_5") (pintype "passive"))
      (node (ref "IC8") (pin "1") (pinfunction "VDD_1") (pintype "bidirectional"))
      (node (ref "IC8") (pin "6") (pinfunction "VS_6") (pintype "bidirectional"))
      (node (ref "IC8") (pin "7") (pinfunction "CS_7") (pintype "bidirectional"))
      (node (ref "IC9") (pin "8") (pinfunction "VDD_8") (pintype "bidirectional"))
      (node (ref "J10") (pin "1") (pinfunction "1_1") (pintype "passive"))
      (node (ref "J12") (pin "1") (pinfunction "1_1") (pintype "passive"))
      (node (ref "J3") (pin "10") (pinfunction "10_10") (pintype "passive"))
      (node (ref "J3") (pin "8") (pinfunction "8_8") (pintype "passive"))
      (node (ref "J8") (pin "1") (pinfunction "1_1") (pintype "passive"))
      (node (ref "J9") (pin "1") (pinfunction "1_1") (pintype "passive"))
    )
    (net (code "76") (name "/XRESET") (class "Default")
      (node (ref "IC1") (pin "11") (pinfunction "XRESET_11") (pintype "bidirectional"))
      (node (ref "R24") (pin "2") (pinfunction "2_2") (pintype "passive"))
    )
    (net (code "77") (name "/XSTBY") (class "Default")
      (node (ref "IC1") (pin "16") (pinfunction "XSTANDBY_16") (pintype "bidirectional"))
      (node (ref "IC4") (pin "20") (pinfunction "PB2_20") (pintype "bidirectional"))
      (node (ref "R25") (pin "2") (pinfunction "2_2") (pintype "passive"))
    )
    (net (code "78") (name "/~{RST}") (class "Default")
      (node (ref "IC4") (pin "7") (pinfunction "~{RST}_7") (pintype "input"))
      (node (ref "J11") (pin "5") (pinfunction "5_5") (pintype "passive"))
      (node (ref "R1") (pin "1") (pinfunction "1_1") (pintype "passive"))
      (node (ref "S1") (pin "2") (pinfunction "2_2") (pintype "passive"))
    )
    (net (code "79") (name "3.3V") (class "Default")
      (node (ref "C1") (pin "1") (pinfunction "1_1") (pintype "passive"))
      (node (ref "C10") (pin "1") (pinfunction "1_1") (pintype "passive"))
      (node (ref "C11") (pin "1") (pinfunction "1_1") (pintype "passive"))
      (node (ref "C12") (pin "1") (pinfunction "1_1") (pintype "passive"))
      (node (ref "C13") (pin "1") (pinfunction "1_1") (pintype "passive"))
      (node (ref "C15") (pin "1") (pinfunction "1_1") (pintype "passive"))
      (node (ref "C16") (pin "1") (pinfunction "1_1") (pintype "passive"))
      (node (ref "C2") (pin "1") (pinfunction "1_1") (pintype "passive"))
      (node (ref "C27") (pin "1") (pinfunction "1_1") (pintype "passive"))
      (node (ref "C3") (pin "1") (pinfunction "1_1") (pintype "passive"))
      (node (ref "D10") (pin "C") (pinfunction "C_C") (pintype "passive"))
      (node (ref "IC1") (pin "12") (pinfunction "VCC_12") (pintype "bidirectional"))
      (node (ref "IC2") (pin "5") (pinfunction "OUT_5") (pintype "passive"))
      (node (ref "IC3") (pin "16") (pinfunction "VCC_16") (pintype "power_in"))
      (node (ref "IC3") (pin "6") (pinfunction "G1_6") (pintype "input"))
      (node (ref "IC4") (pin "1") (pinfunction "VLCD_1") (pintype "power_in"))
      (node (ref "IC4") (pin "24") (pinfunction "VDD_24") (pintype "power_in"))
      (node (ref "IC4") (pin "36") (pinfunction "VDD_USB_36") (pintype "power_in"))
      (node (ref "IC4") (pin "48") (pinfunction "VDD_48") (pintype "power_in"))
      (node (ref "J1") (pin "2") (pinfunction "2_2") (pintype "passive"))
      (node (ref "J11") (pin "1") (pinfunction "1_1") (pintype "passive"))
      (node (ref "J13") (pin "7") (pinfunction "7_7") (pintype "passive"))
      (node (ref "J13") (pin "8") (pinfunction "8_8") (pintype "passive"))
      (node (ref "J2") (pin "2") (pinfunction "2_2") (pintype "passive"))
      (node (ref "J4") (pin "4") (pinfunction "VCC_4") (pintype "bidirectional"))
      (node (ref "L2") (pin "1") (pinfunction "1_1") (pintype "passive"))
      (node (ref "R1") (pin "2") (pinfunction "2_2") (pintype "passive"))
      (node (ref "R2") (pin "2") (pinfunction "1_2") (pintype "passive"))
      (node (ref "R2") (pin "3") (pinfunction "1_3") (pintype "passive"))
      (node (ref "R2") (pin "4") (pinfunction "1_4") (pintype "passive"))
      (node (ref "R24") (pin "1") (pinfunction "1_1") (pintype "passive"))
      (node (ref "R25") (pin "1") (pinfunction "1_1") (pintype "passive"))
      (node (ref "R26") (pin "2") (pinfunction "2_2") (pintype "passive"))
      (node (ref "R4") (pin "2") (pinfunction "2_2") (pintype "passive"))
      (node (ref "R6") (pin "2") (pinfunction "2_2") (pintype "passive"))
      (node (ref "R7") (pin "2") (pinfunction "2_2") (pintype "passive"))
    )
    (net (code "80") (name "5V") (class "Default")
      (node (ref "C14") (pin "1") (pinfunction "1_1") (pintype "passive"))
      (node (ref "C17") (pin "1") (pinfunction "1_1") (pintype "passive"))
      (node (ref "C19") (pin "1") (pinfunction "1_1") (pintype "passive"))
      (node (ref "C20") (pin "1") (pinfunction "1_1") (pintype "passive"))
      (node (ref "C22") (pin "1") (pinfunction "1_1") (pintype "passive"))
      (node (ref "C26") (pin "1") (pinfunction "1_1") (pintype "passive"))
      (node (ref "C34") (pin "1") (pinfunction "1_1") (pintype "passive"))
      (node (ref "D2") (pin "C") (pinfunction "C_C") (pintype "passive"))
      (node (ref "D3") (pin "1") (pinfunction "GRN-A_1") (pintype "bidirectional"))
      (node (ref "D3") (pin "2") (pinfunction "RED-A_2") (pintype "bidirectional"))
      (node (ref "D3") (pin "3") (pinfunction "BLU-A_3") (pintype "bidirectional"))
      (node (ref "IC10") (pin "1") (pinfunction "IN_1") (pintype "input"))
      (node (ref "IC2") (pin "1") (pinfunction "IN_1") (pintype "input"))
      (node (ref "IC5") (pin "6") (pinfunction "VOS_6") (pintype "input"))
      (node (ref "IC6") (pin "5") (pinfunction "VCC_5") (pintype "power_in"))
      (node (ref "IC7") (pin "8") (pinfunction "V+_8") (pintype "power_in"))
      (node (ref "L1") (pin "2") (pinfunction "2_2") (pintype "passive"))
      (node (ref "R10\\") (pin "2") (pinfunction "2_2") (pintype "passive"))
      (node (ref "R16") (pin "2") (pinfunction "2_2") (pintype "passive"))
      (node (ref "R23") (pin "2") (pinfunction "2_2") (pintype "passive"))
      (node (ref "R9") (pin "2") (pinfunction "2_2") (pintype "passive"))
    )
    (net (code "81") (name "AGND") (class "Default")
      (node (ref "IC1") (pin "2") (pinfunction "GND_2") (pintype "bidirectional"))
      (node (ref "IC1") (pin "4") (pinfunction "GND_4") (pintype "bidirectional"))
      (node (ref "J7") (pin "GND@0") (pinfunction "GND_GND@0") (pintype "bidirectional"))
      (node (ref "J7") (pin "GND@1") (pinfunction "GND_GND@1") (pintype "bidirectional"))
      (node (ref "J7") (pin "GND@2") (pinfunction "GND_GND@2") (pintype "bidirectional"))
      (node (ref "J7") (pin "GND@3") (pinfunction "GND_GND@3") (pintype "bidirectional"))
      (node (ref "JP1") (pin "1") (pinfunction "1_1") (pintype "passive"))
    )
    (net (code "82") (name "GND") (class "Default")
      (node (ref "C1") (pin "2") (pinfunction "2_2") (pintype "passive"))
      (node (ref "C10") (pin "2") (pinfunction "2_2") (pintype "passive"))
      (node (ref "C11") (pin "2") (pinfunction "2_2") (pintype "passive"))
      (node (ref "C12") (pin "2") (pinfunction "2_2") (pintype "passive"))
      (node (ref "C13") (pin "2") (pinfunction "2_2") (pintype "passive"))
      (node (ref "C14") (pin "2") (pinfunction "2_2") (pintype "passive"))
      (node (ref "C15") (pin "2") (pinfunction "2_2") (pintype "passive"))
      (node (ref "C16") (pin "2") (pinfunction "2_2") (pintype "passive"))
      (node (ref "C17") (pin "2") (pinfunction "2_2") (pintype "passive"))
      (node (ref "C18") (pin "2") (pinfunction "2_2") (pintype "passive"))
      (node (ref "C19") (pin "2") (pinfunction "2_2") (pintype "passive"))
      (node (ref "C2") (pin "2") (pinfunction "2_2") (pintype "passive"))
      (node (ref "C20") (pin "2") (pinfunction "2_2") (pintype "passive"))
      (node (ref "C21") (pin "2") (pinfunction "-_2") (pintype "passive"))
      (node (ref "C22") (pin "2") (pinfunction "2_2") (pintype "passive"))
      (node (ref "C23") (pin "2") (pinfunction "2_2") (pintype "passive"))
      (node (ref "C24") (pin "2") (pinfunction "2_2") (pintype "passive"))
      (node (ref "C26") (pin "2") (pinfunction "2_2") (pintype "passive"))
      (node (ref "C27") (pin "2") (pinfunction "2_2") (pintype "passive"))
      (node (ref "C28") (pin "2") (pinfunction "2_2") (pintype "passive"))
      (node (ref "C29") (pin "2") (pinfunction "2_2") (pintype "passive"))
      (node (ref "C3") (pin "2") (pinfunction "2_2") (pintype "passive"))
      (node (ref "C30") (pin "2") (pinfunction "2_2") (pintype "passive"))
      (node (ref "C31") (pin "2") (pinfunction "2_2") (pintype "passive"))
      (node (ref "C32") (pin "2") (pinfunction "2_2") (pintype "passive"))
      (node (ref "C33") (pin "2") (pinfunction "2_2") (pintype "passive"))
      (node (ref "C34") (pin "2") (pinfunction "2_2") (pintype "passive"))
      (node (ref "C35") (pin "2") (pinfunction "2_2") (pintype "passive"))
      (node (ref "C36") (pin "2") (pinfunction "2_2") (pintype "passive"))
      (node (ref "C39") (pin "2") (pinfunction "2_2") (pintype "passive"))
      (node (ref "C4") (pin "2") (pinfunction "2_2") (pintype "passive"))
      (node (ref "C5") (pin "2") (pinfunction "2_2") (pintype "passive"))
      (node (ref "C6") (pin "2") (pinfunction "2_2") (pintype "passive"))
      (node (ref "C7") (pin "2") (pinfunction "2_2") (pintype "passive"))
      (node (ref "C8") (pin "2") (pinfunction "2_2") (pintype "passive"))
      (node (ref "C9") (pin "2") (pinfunction "2_2") (pintype "passive"))
      (node (ref "D1") (pin "A") (pinfunction "A_A") (pintype "passive"))
      (node (ref "D10") (pin "A") (pinfunction "A_A") (pintype "passive"))
      (node (ref "D2") (pin "A") (pinfunction "A_A") (pintype "passive"))
      (node (ref "D4") (pin "A") (pinfunction "A_A") (pintype "passive"))
      (node (ref "D5") (pin "A") (pinfunction "A_A") (pintype "passive"))
      (node (ref "D6") (pin "2") (pinfunction "GND_2") (pintype "power_in"))
      (node (ref "D7") (pin "A") (pinfunction "A_A") (pintype "passive"))
      (node (ref "D8") (pin "A") (pinfunction "A_A") (pintype "passive"))
      (node (ref "D9") (pin "A") (pinfunction "A_A") (pintype "passive"))
      (node (ref "IC1") (pin "1") (pinfunction "GND_1") (pintype "bidirectional"))
      (node (ref "IC1") (pin "13") (pinfunction "GND_13") (pintype "bidirectional"))
      (node (ref "IC1") (pin "14") (pinfunction "GND_14") (pintype "bidirectional"))
      (node (ref "IC1") (pin "15") (pinfunction "GND_15") (pintype "bidirectional"))
      (node (ref "IC1") (pin "27") (pinfunction "GND_27") (pintype "bidirectional"))
      (node (ref "IC1") (pin "28") (pinfunction "GND_28") (pintype "bidirectional"))
      (node (ref "IC10") (pin "2") (pinfunction "GND_2") (pintype "power_in"))
      (node (ref "IC2") (pin "2") (pinfunction "GND_2") (pintype "power_in"))
      (node (ref "IC3") (pin "5") (pinfunction "G2_5") (pintype "input"))
      (node (ref "IC3") (pin "8") (pinfunction "GND_8") (pintype "power_in"))
      (node (ref "IC4") (pin "23") (pinfunction "VSS_23") (pintype "power_in"))
      (node (ref "IC4") (pin "35") (pinfunction "VSS_35") (pintype "power_in"))
      (node (ref "IC4") (pin "47") (pinfunction "VSS_47") (pintype "power_in"))
      (node (ref "IC4") (pin "8") (pinfunction "VSSA_8") (pintype "power_in"))
      (node (ref "IC5") (pin "1") (pinfunction "GND_1") (pintype "power_in"))
      (node (ref "IC5") (pin "4") (pinfunction "GND_4") (pintype "power_in"))
      (node (ref "IC6") (pin "6") (pinfunction "GND_6") (pintype "power_in"))
      (node (ref "IC7") (pin "4") (pinfunction "V-_4") (pintype "power_in"))
      (node (ref "IC8") (pin "2") (pinfunction "GND_2") (pintype "bidirectional"))
      (node (ref "IC8") (pin "4") (pinfunction "GND_4") (pintype "bidirectional"))
      (node (ref "IC8") (pin "5") (pinfunction "GND_5") (pintype "bidirectional"))
      (node (ref "IC9") (pin "2") (pinfunction "GND_2") (pintype "bidirectional"))
      (node (ref "J1") (pin "1") (pinfunction "1_1") (pintype "passive"))
      (node (ref "J10") (pin "2") (pinfunction "2_2") (pintype "passive"))
      (node (ref "J11") (pin "3") (pinfunction "3_3") (pintype "passive"))
      (node (ref "J12") (pin "2") (pinfunction "2_2") (pintype "passive"))
      (node (ref "J13") (pin "1") (pinfunction "1_1") (pintype "passive"))
      (node (ref "J13") (pin "5") (pinfunction "5_5") (pintype "passive"))
      (node (ref "J2") (pin "1") (pinfunction "1_1") (pintype "passive"))
      (node (ref "J3") (pin "1") (pinfunction "1_1") (pintype "passive"))
      (node (ref "J3") (pin "5") (pinfunction "5_5") (pintype "passive"))
      (node (ref "J4") (pin "6") (pinfunction "GND_6") (pintype "bidirectional"))
      (node (ref "J4") (pin "CD1") (pinfunction "CD1_CD1") (pintype "bidirectional"))
      (node (ref "J4") (pin "CD2") (pinfunction "CD2_CD2") (pintype "bidirectional"))
      (node (ref "J4") (pin "GND1") (pinfunction "SHIELD_GND1") (pintype "bidirectional"))
      (node (ref "J4") (pin "GND3") (pinfunction "SHIELD_GND3") (pintype "bidirectional"))
      (node (ref "J5") (pin "1") (pinfunction "1_1") (pintype "passive"))
      (node (ref "J8") (pin "2") (pinfunction "2_2") (pintype "passive"))
      (node (ref "J9") (pin "2") (pinfunction "2_2") (pintype "passive"))
      (node (ref "JP1") (pin "2") (pinfunction "2_2") (pintype "passive"))
      (node (ref "JP2") (pin "2") (pinfunction "2_2") (pintype "passive"))
      (node (ref "R10") (pin "1") (pinfunction "1_1") (pintype "passive"))
      (node (ref "R11") (pin "1") (pinfunction "1_1") (pintype "passive"))
      (node (ref "R12") (pin "1") (pinfunction "1_1") (pintype "passive"))
      (node (ref "R17") (pin "1") (pinfunction "1_1") (pintype "passive"))
      (node (ref "R20") (pin "1") (pinfunction "1_1") (pintype "passive"))
      (node (ref "S1") (pin "1") (pinfunction "1_1") (pintype "passive"))
      (node (ref "S2") (pin "1") (pinfunction "1_1") (pintype "passive"))
    )
    (net (code "83") (name "unconnected-(IC1-LNA-Pad5)") (class "Default")
      (node (ref "IC1") (pin "5") (pinfunction "LNA_5") (pintype "bidirectional"))
    )
    (net (code "84") (name "unconnected-(IC1-OPEN-Pad7)") (class "Default")
      (node (ref "IC1") (pin "7") (pinfunction "OPEN_7") (pintype "bidirectional"))
    )
    (net (code "85") (name "unconnected-(IC1-RESERVED1-Pad6)") (class "Default")
      (node (ref "IC1") (pin "6") (pinfunction "RESERVED1_6") (pintype "bidirectional"))
    )
    (net (code "86") (name "unconnected-(IC1-RESERVED2-Pad9)") (class "Default")
      (node (ref "IC1") (pin "9") (pinfunction "RESERVED2_9") (pintype "bidirectional"))
    )
    (net (code "87") (name "unconnected-(IC1-RESERVED3-Pad17)") (class "Default")
      (node (ref "IC1") (pin "17") (pinfunction "RESERVED3_17") (pintype "bidirectional"))
    )
    (net (code "88") (name "unconnected-(IC1-RESERVED4-Pad18)") (class "Default")
      (node (ref "IC1") (pin "18") (pinfunction "RESERVED4_18") (pintype "bidirectional"))
    )
    (net (code "89") (name "unconnected-(IC1-RESERVED5-Pad22)") (class "Default")
      (node (ref "IC1") (pin "22") (pinfunction "RESERVED5_22") (pintype "bidirectional"))
    )
    (net (code "90") (name "unconnected-(IC1-RESERVED6-Pad25)") (class "Default")
      (node (ref "IC1") (pin "25") (pinfunction "RESERVED6_25") (pintype "bidirectional"))
    )
    (net (code "91") (name "unconnected-(IC1-RESERVED7-Pad26)") (class "Default")
      (node (ref "IC1") (pin "26") (pinfunction "RESERVED7_26") (pintype "bidirectional"))
    )
    (net (code "92") (name "unconnected-(IC1-SHORT-Pad8)") (class "Default")
      (node (ref "IC1") (pin "8") (pinfunction "SHORT_8") (pintype "bidirectional"))
    )
    (net (code "93") (name "unconnected-(IC2-NC{slash}FB-Pad4)") (class "Default")
      (node (ref "IC2") (pin "4") (pinfunction "NC/FB_4") (pintype "passive"))
    )
    (net (code "94") (name "unconnected-(IC2-~{EN}-Pad3)") (class "Default")
      (node (ref "IC2") (pin "3") (pinfunction "~{EN}_3") (pintype "input"))
    )
    (net (code "95") (name "unconnected-(IC3A-Y6-Pad9)") (class "Default")
      (node (ref "IC3") (pin "9") (pinfunction "Y6_9") (pintype "output"))
    )
    (net (code "96") (name "unconnected-(IC3A-Y7-Pad7)") (class "Default")
      (node (ref "IC3") (pin "7") (pinfunction "Y7_7") (pintype "output"))
    )
    (net (code "97") (name "unconnected-(IC4-PA9-Pad30)") (class "Default")
      (node (ref "IC4") (pin "30") (pinfunction "PA9_30") (pintype "bidirectional"))
    )
    (net (code "98") (name "unconnected-(IC4-PA10-Pad31)") (class "Default")
      (node (ref "IC4") (pin "31") (pinfunction "PA10_31") (pintype "bidirectional"))
    )
    (net (code "99") (name "unconnected-(IC8-NC-Pad3)") (class "Default")
      (node (ref "IC8") (pin "3") (pinfunction "NC_3") (pintype "bidirectional"))
    )
    (net (code "100") (name "unconnected-(IC8-NC-Pad10)") (class "Default")
      (node (ref "IC8") (pin "10") (pinfunction "NC_10") (pintype "bidirectional"))
    )
    (net (code "101") (name "unconnected-(IC8-NC-Pad11)") (class "Default")
      (node (ref "IC8") (pin "11") (pinfunction "NC_11") (pintype "bidirectional"))
    )
    (net (code "102") (name "unconnected-(IC9-NC-Pad7)") (class "Default")
      (node (ref "IC9") (pin "7") (pinfunction "NC_7") (pintype "bidirectional"))
    )
    (net (code "103") (name "unconnected-(IC10-NC{slash}FB-Pad4)") (class "Default")
      (node (ref "IC10") (pin "4") (pinfunction "NC/FB_4") (pintype "passive"))
    )
    (net (code "104") (name "unconnected-(IC10-~{EN}-Pad3)") (class "Default")
      (node (ref "IC10") (pin "3") (pinfunction "~{EN}_3") (pintype "input"))
    )
    (net (code "105") (name "unconnected-(J4-NC-Pad1)") (class "Default")
      (node (ref "J4") (pin "1") (pinfunction "NC_1") (pintype "bidirectional"))
    )
    (net (code "106") (name "unconnected-(J4-RSV-Pad8)") (class "Default")
      (node (ref "J4") (pin "8") (pinfunction "RSV_8") (pintype "bidirectional"))
    )
    (net (code "107") (name "unconnected-(J11-Pad6)") (class "Default")
      (node (ref "J11") (pin "6") (pinfunction "6_6") (pintype "passive"))
    )
  )
)
